# Gadget-Box-ESP8266-Modules.net
KiCad netlist of a schematic drawn in EAGLE
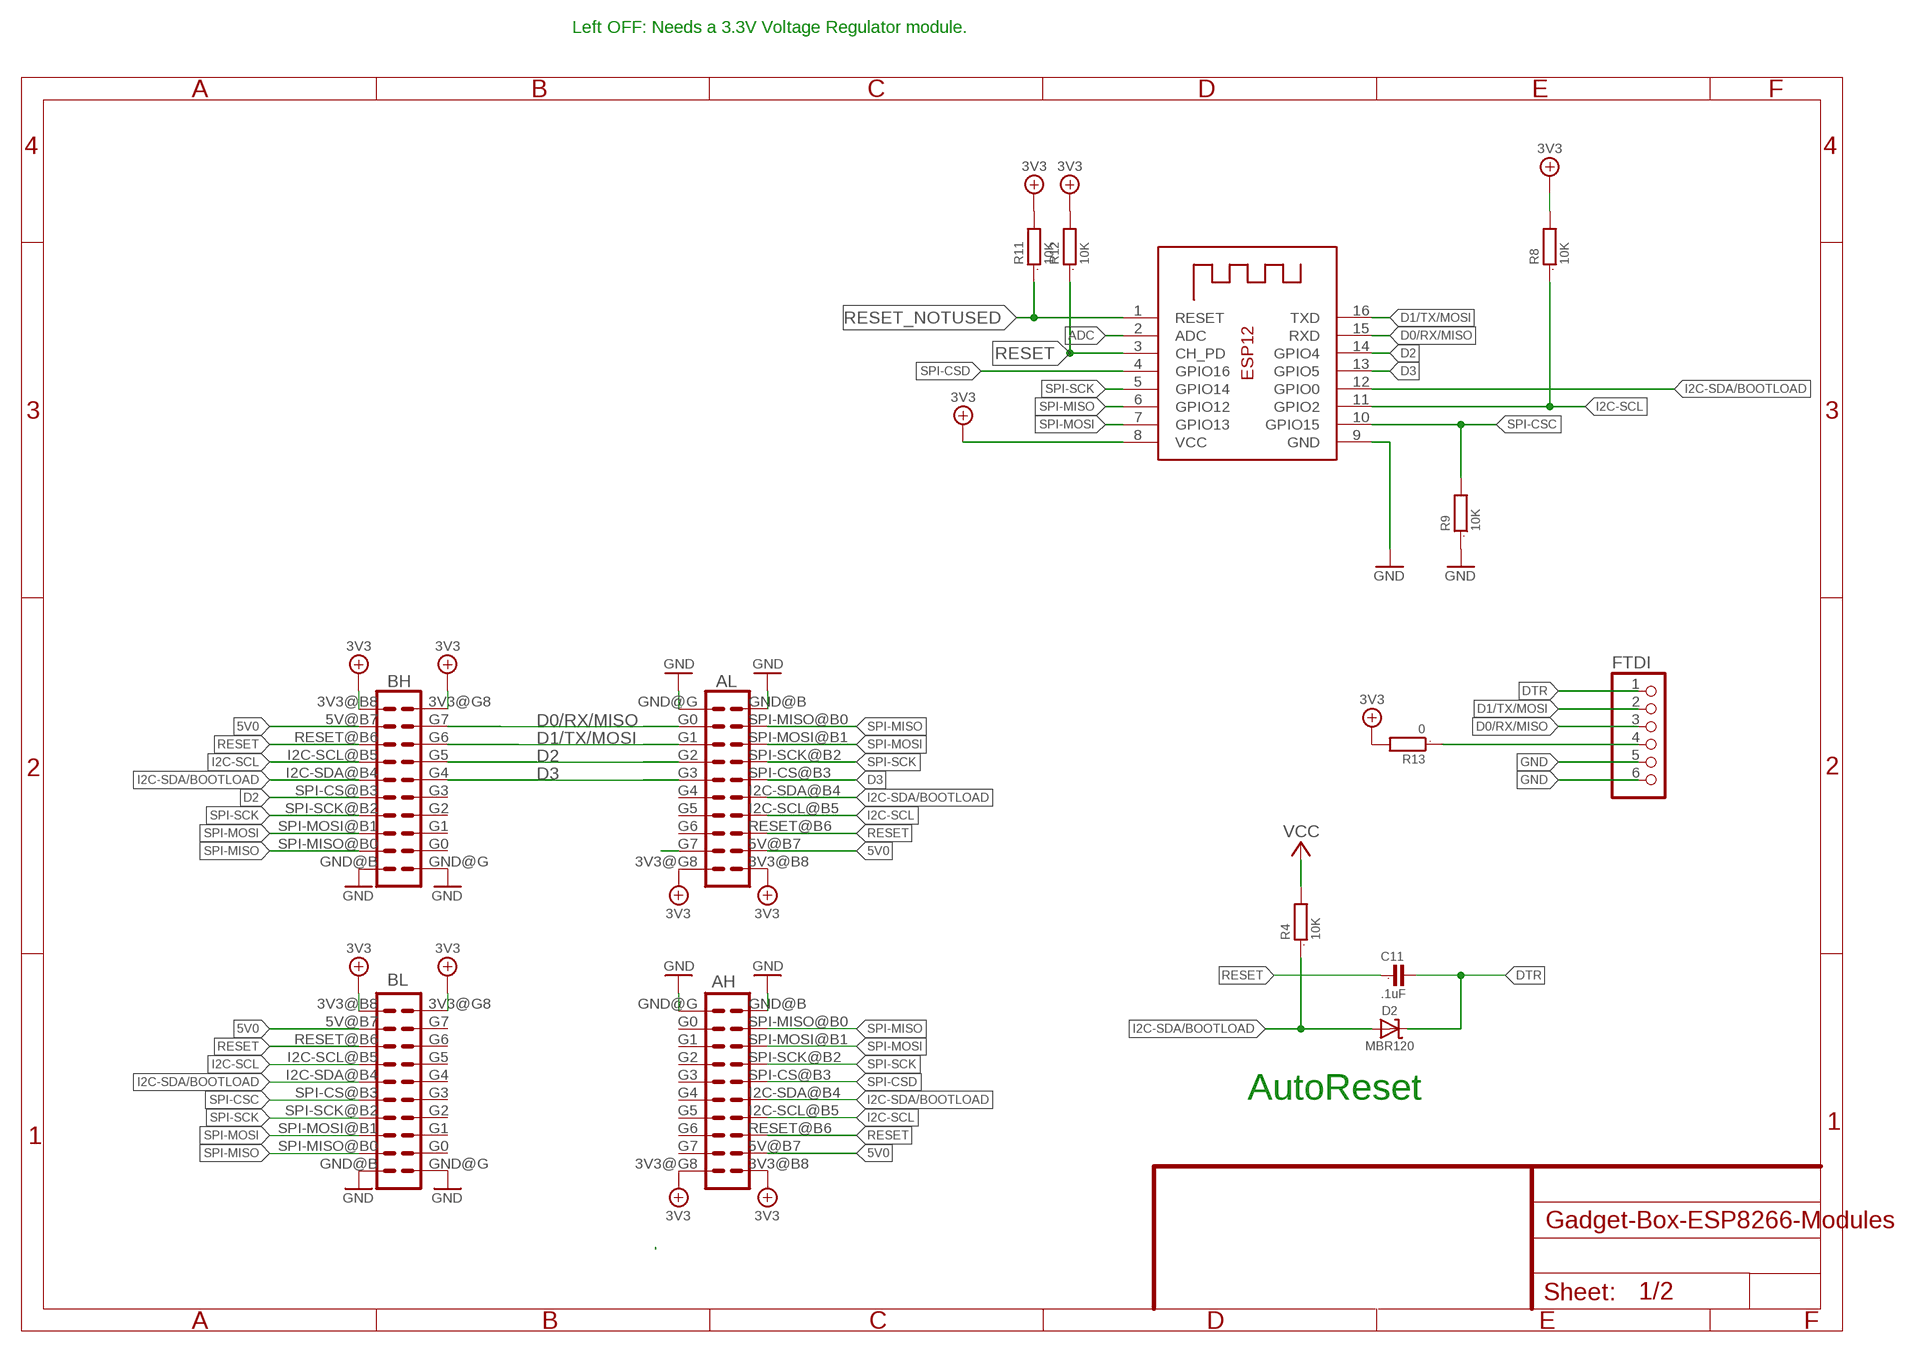
[diagram p0: schematic, sheet 1]
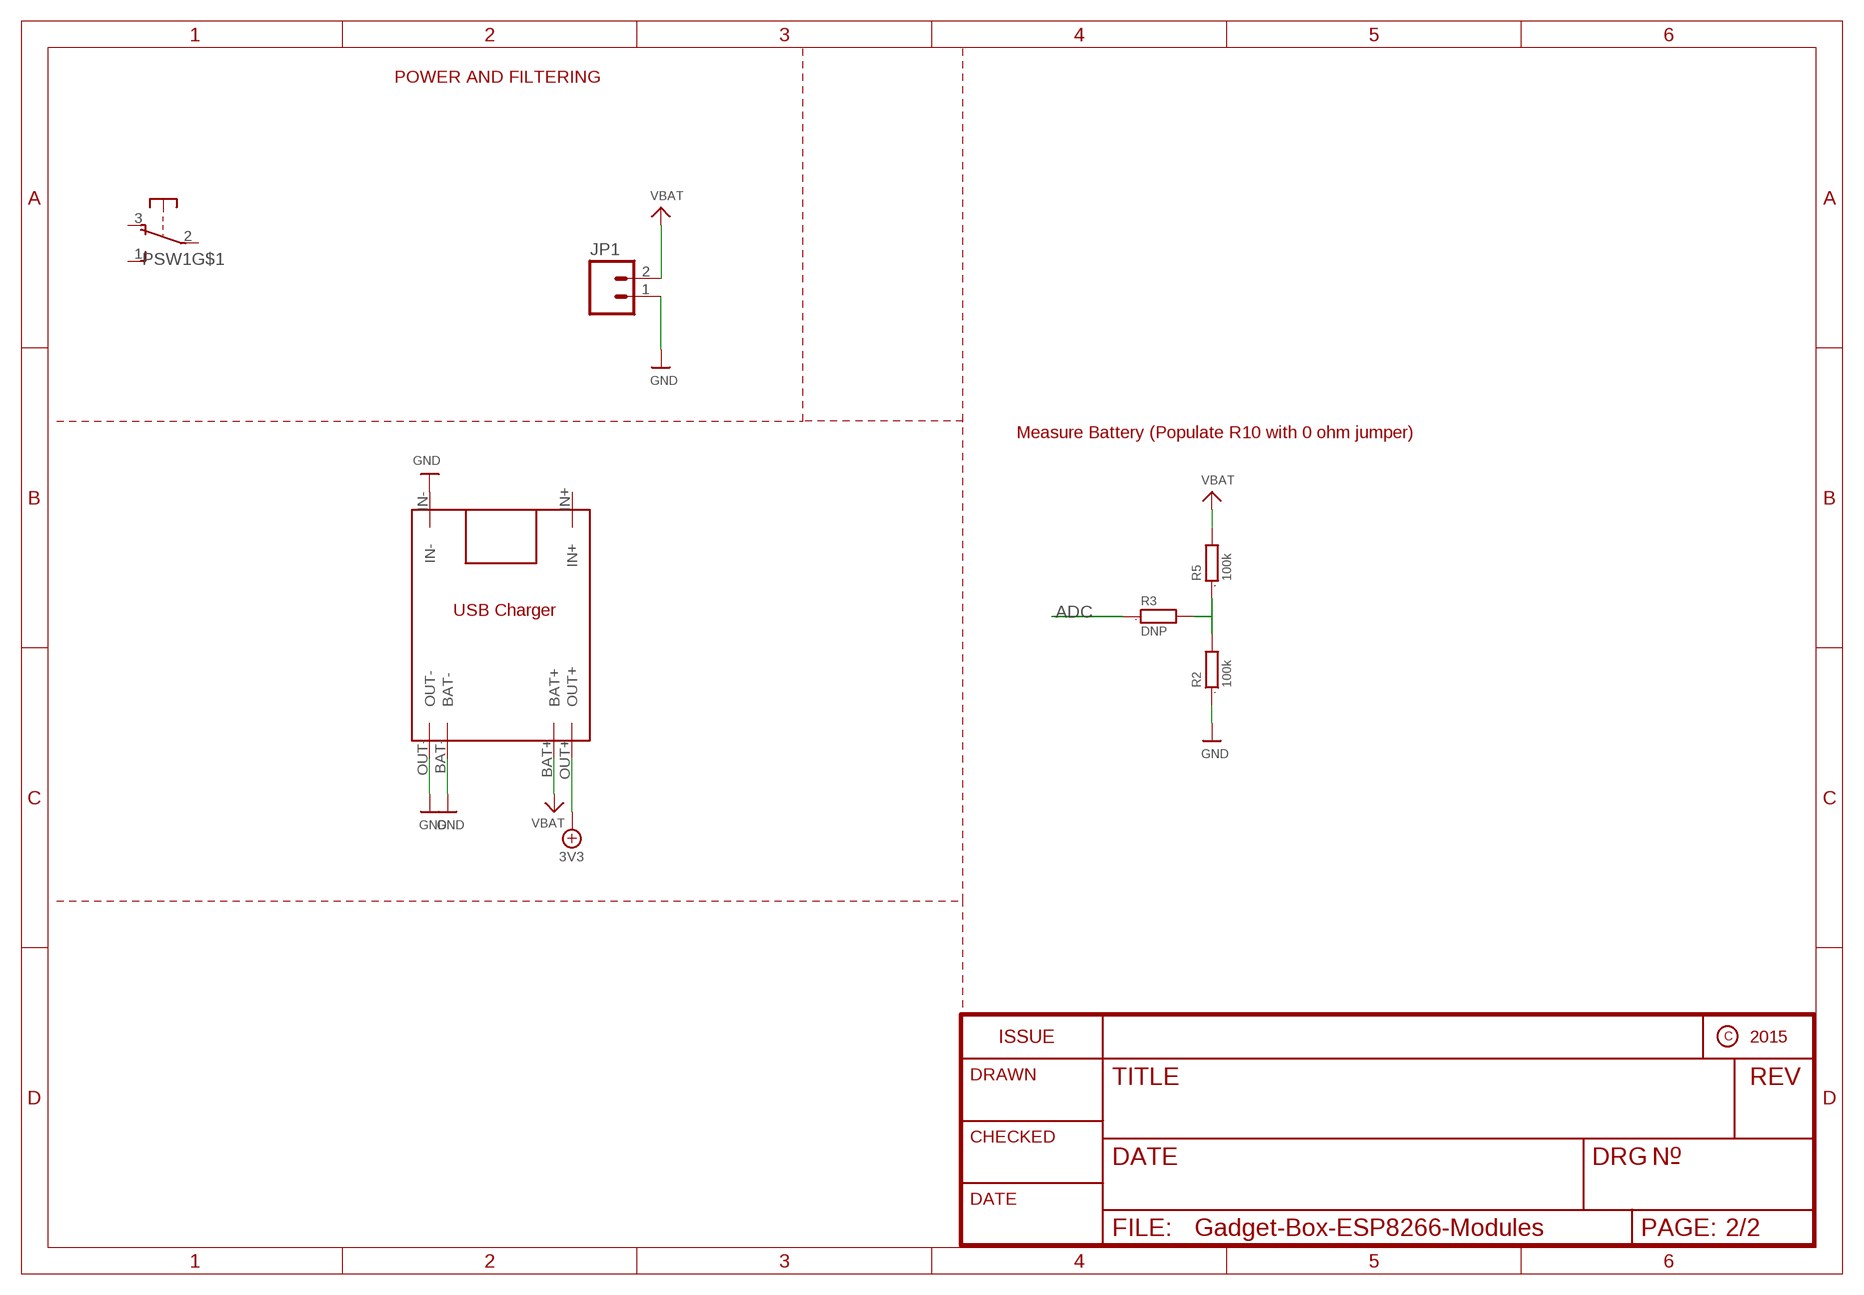
[diagram p1: schematic, sheet 2]

(export (version "E")
  (design (tool "Eeschema 10.0.6"))
  (components
    (comp (ref "JP1")
      (value "M02-JST-2-PTH-NO_SILK")
      (footprint "eagle-import:JST-2-PTH-NS")
      (libsource (lib "eagle-import") (part "M02-JST-2-PTH-NO_SILK"))
    )
    (comp (ref "PSW1")
      (value "OS102011MA1Q")
      (footprint "eagle-import:OS102011MA1Q")
      (fields
        (field (name "PARTNO") "OS102011MA1QN1,C&K Components,dk,CKN9559-ND,SWITCH SLIDE SPDT 100MA 12V , REF72")
      )
      (libsource (lib "eagle-import") (part "OS102011MA1Q"))
    )
    (comp (ref "R2")
      (value "100k")
      (footprint "eagle-import:0603")
      (fields
        (field (name "PARTNO") "RC0603JR-07100KL,YAGEO (VA),dk,311-100KGRCT-ND,RES SMD 100K OHM 5% 1/10W 0603 , REF76")
      )
      (libsource (lib "eagle-import") (part "R0603"))
    )
    (comp (ref "R3")
      (value "DNP")
      (footprint "eagle-import:0603")
      (libsource (lib "eagle-import") (part "R0603"))
    )
    (comp (ref "R5")
      (value "100k")
      (footprint "eagle-import:0603")
      (fields
        (field (name "PARTNO") "RC0603JR-07100KL,YAGEO (VA),dk,311-100KGRCT-ND,RES SMD 100K OHM 5% 1/10W 0603 , REF76")
      )
      (libsource (lib "eagle-import") (part "R0603"))
    )
    (comp (ref "U$1")
      (value "TP4056")
      (footprint "eagle-import:TP4056")
      (libsource (lib "eagle-import") (part "TP4056"))
    )
    (comp (ref "AH")
      (value "ECOGECOG_SLOT")
      (footprint "eagle-import:ECOG")
      (libsource (lib "eagle-import") (part "ECOGECOG_SLOT"))
    )
    (comp (ref "AL")
      (value "ECOGECOG_SLOT")
      (footprint "eagle-import:ECOG")
      (libsource (lib "eagle-import") (part "ECOGECOG_SLOT"))
    )
    (comp (ref "BH")
      (value "ECOGECOG_SLOT")
      (footprint "eagle-import:ECOG")
      (libsource (lib "eagle-import") (part "ECOGECOG_SLOT"))
    )
    (comp (ref "BL")
      (value "ECOGECOG_SLOT")
      (footprint "eagle-import:ECOG")
      (libsource (lib "eagle-import") (part "ECOGECOG_SLOT"))
    )
    (comp (ref "C11")
      (value ".1uF")
      (footprint "eagle-import:0805")
      (fields
        (field (name "PARTNO") "GRM21BR71E104KA01L,MURATA ELECTRONICS (VA),DK,490-1673-1-ND,CAP CER .1UF 25V 10% X7R 0805, REF3")
      )
      (libsource (lib "eagle-import") (part "C0805"))
    )
    (comp (ref "D2")
      (value "MBR120")
      (footprint "eagle-import:SOD-123")
      (fields
        (field (name "PARTNO") "MBR120VLSFT3G,on semiconductor,dk,MBR120VLSFT3GOSCT-ND ,DIODE SCHOTTKY 20V 1A SOD123FL , REF71")
      )
      (libsource (lib "eagle-import") (part "DIODE-SCHOTTKYSOD-123"))
    )
    (comp (ref "FTDI")
      (value "PINHD-1X6")
      (footprint "eagle-import:1X06")
      (libsource (lib "eagle-import") (part "PINHD-1X6"))
    )
    (comp (ref "R4")
      (value "10K")
      (footprint "eagle-import:0805")
      (fields
        (field (name "PARTNO") "RC0805JR-0710KL,YAGEO (VA),dk,311-10KARCT-ND,RES SMD 10K OHM 5% 1/8W 0805, REF63")
      )
      (libsource (lib "eagle-import") (part "R0805"))
    )
    (comp (ref "R8")
      (value "10K")
      (footprint "eagle-import:0805")
      (fields
        (field (name "PARTNO") "RC0805JR-0710KL,YAGEO (VA),dk,311-10KARCT-ND,RES SMD 10K OHM 5% 1/8W 0805, REF63")
      )
      (libsource (lib "eagle-import") (part "R0805"))
    )
    (comp (ref "R9")
      (value "10K")
      (footprint "eagle-import:0805")
      (fields
        (field (name "PARTNO") "RC0805JR-0710KL,YAGEO (VA),dk,311-10KARCT-ND,RES SMD 10K OHM 5% 1/8W 0805, REF63")
      )
      (libsource (lib "eagle-import") (part "R0805"))
    )
    (comp (ref "R11")
      (value "10K")
      (footprint "eagle-import:0805")
      (fields
        (field (name "PARTNO") "RC0805JR-0710KL,YAGEO (VA),dk,311-10KARCT-ND,RES SMD 10K OHM 5% 1/8W 0805, REF63")
      )
      (libsource (lib "eagle-import") (part "R0805"))
    )
    (comp (ref "R12")
      (value "10K")
      (footprint "eagle-import:0805")
      (fields
        (field (name "PARTNO") "RC0805JR-0710KL,YAGEO (VA),dk,311-10KARCT-ND,RES SMD 10K OHM 5% 1/8W 0805, REF63")
      )
      (libsource (lib "eagle-import") (part "R0805"))
    )
    (comp (ref "R13")
      (value "0")
      (footprint "eagle-import:0805")
      (libsource (lib "eagle-import") (part "R0805"))
    )
    (comp (ref "X2")
      (value "ESP-12")
      (footprint "eagle-import:ESP-12")
      (libsource (lib "eagle-import") (part "ESP-12"))
    )
  )
  (nets
    (net (code "1") (name "3V3") (class "Default")
      (node (ref "AH") (pin "3V3@B8") (pinfunction "3V3_3V3@B8") (pintype "passive"))
      (node (ref "AH") (pin "3V3@G8") (pinfunction "3V3_3V3@G8") (pintype "passive"))
      (node (ref "AL") (pin "3V3@B8") (pinfunction "3V3_3V3@B8") (pintype "passive"))
      (node (ref "AL") (pin "3V3@G8") (pinfunction "3V3_3V3@G8") (pintype "passive"))
      (node (ref "BH") (pin "3V3@B8") (pinfunction "3V3_3V3@B8") (pintype "passive"))
      (node (ref "BH") (pin "3V3@G8") (pinfunction "3V3_3V3@G8") (pintype "passive"))
      (node (ref "BL") (pin "3V3@B8") (pinfunction "3V3_3V3@B8") (pintype "passive"))
      (node (ref "BL") (pin "3V3@G8") (pinfunction "3V3_3V3@G8") (pintype "passive"))
      (node (ref "R11") (pin "2") (pinfunction "2_2") (pintype "passive"))
      (node (ref "R12") (pin "2") (pinfunction "2_2") (pintype "passive"))
      (node (ref "R13") (pin "2") (pinfunction "2_2") (pintype "passive"))
      (node (ref "R8") (pin "2") (pinfunction "2_2") (pintype "passive"))
      (node (ref "U$1") (pin "OUT+") (pinfunction "OUT+_OUT+") (pintype "bidirectional"))
      (node (ref "X2") (pin "8") (pinfunction "VCC_8") (pintype "power_in"))
    )
    (net (code "2") (name "5V0") (class "Default")
      (node (ref "AH") (pin "5V@B7") (pinfunction "5V_5V@B7") (pintype "passive"))
      (node (ref "AL") (pin "5V@B7") (pinfunction "5V_5V@B7") (pintype "passive"))
      (node (ref "BH") (pin "5V@B7") (pinfunction "5V_5V@B7") (pintype "passive"))
      (node (ref "BL") (pin "5V@B7") (pinfunction "5V_5V@B7") (pintype "passive"))
    )
    (net (code "3") (name "ADC") (class "Default")
      (node (ref "R3") (pin "1") (pinfunction "1_1") (pintype "passive"))
      (node (ref "X2") (pin "2") (pinfunction "ADC_2") (pintype "passive"))
    )
    (net (code "4") (name "D0{slash}RX{slash}MISO") (class "Default")
      (node (ref "AL") (pin "G0") (pinfunction "G0_G0") (pintype "passive"))
      (node (ref "BH") (pin "G7") (pinfunction "G7_G7") (pintype "passive"))
      (node (ref "FTDI") (pin "3") (pinfunction "3_3") (pintype "passive"))
      (node (ref "X2") (pin "15") (pinfunction "RXD_15") (pintype "input"))
    )
    (net (code "5") (name "D1{slash}TX{slash}MOSI") (class "Default")
      (node (ref "AL") (pin "G1") (pinfunction "G1_G1") (pintype "passive"))
      (node (ref "BH") (pin "G6") (pinfunction "G6_G6") (pintype "passive"))
      (node (ref "FTDI") (pin "2") (pinfunction "2_2") (pintype "passive"))
      (node (ref "X2") (pin "16") (pinfunction "TXD_16") (pintype "output"))
    )
    (net (code "6") (name "D2") (class "Default")
      (node (ref "AL") (pin "G2") (pinfunction "G2_G2") (pintype "passive"))
      (node (ref "BH") (pin "G5") (pinfunction "G5_G5") (pintype "passive"))
      (node (ref "BH") (pin "SPI-CS@B3") (pinfunction "SPI-CS_SPI-CS@B3") (pintype "passive"))
      (node (ref "X2") (pin "14") (pinfunction "GPIO4_14") (pintype "bidirectional"))
    )
    (net (code "7") (name "D3") (class "Default")
      (node (ref "AL") (pin "G3") (pinfunction "G3_G3") (pintype "passive"))
      (node (ref "AL") (pin "SPI-CS@B3") (pinfunction "SPI-CS_SPI-CS@B3") (pintype "passive"))
      (node (ref "BH") (pin "G4") (pinfunction "G4_G4") (pintype "passive"))
      (node (ref "X2") (pin "13") (pinfunction "GPIO5_13") (pintype "bidirectional"))
    )
    (net (code "8") (name "DTR") (class "Default")
      (node (ref "C11") (pin "2") (pinfunction "2_2") (pintype "passive"))
      (node (ref "D2") (pin "C") (pinfunction "C_C") (pintype "passive"))
      (node (ref "FTDI") (pin "1") (pinfunction "1_1") (pintype "passive"))
    )
    (net (code "9") (name "GND") (class "Default")
      (node (ref "AH") (pin "GND@B") (pinfunction "GND_GND@B") (pintype "passive"))
      (node (ref "AH") (pin "GND@G") (pinfunction "GND_GND@G") (pintype "passive"))
      (node (ref "AL") (pin "GND@B") (pinfunction "GND_GND@B") (pintype "passive"))
      (node (ref "AL") (pin "GND@G") (pinfunction "GND_GND@G") (pintype "passive"))
      (node (ref "BH") (pin "GND@B") (pinfunction "GND_GND@B") (pintype "passive"))
      (node (ref "BH") (pin "GND@G") (pinfunction "GND_GND@G") (pintype "passive"))
      (node (ref "BL") (pin "GND@B") (pinfunction "GND_GND@B") (pintype "passive"))
      (node (ref "BL") (pin "GND@G") (pinfunction "GND_GND@G") (pintype "passive"))
      (node (ref "FTDI") (pin "5") (pinfunction "5_5") (pintype "passive"))
      (node (ref "FTDI") (pin "6") (pinfunction "6_6") (pintype "passive"))
      (node (ref "JP1") (pin "1") (pinfunction "1_1") (pintype "passive"))
      (node (ref "R2") (pin "1") (pinfunction "1_1") (pintype "passive"))
      (node (ref "R9") (pin "1") (pinfunction "1_1") (pintype "passive"))
      (node (ref "U$1") (pin "BAT-") (pinfunction "BAT-_BAT-") (pintype "bidirectional"))
      (node (ref "U$1") (pin "IN-") (pinfunction "IN-_IN-") (pintype "bidirectional"))
      (node (ref "U$1") (pin "OUT-") (pinfunction "OUT-_OUT-") (pintype "bidirectional"))
      (node (ref "X2") (pin "9") (pinfunction "GND_9") (pintype "power_in"))
    )
    (net (code "10") (name "I2C-SCL") (class "Default")
      (node (ref "AH") (pin "I2C-SCL@B5") (pinfunction "I2C-SCL_I2C-SCL@B5") (pintype "passive"))
      (node (ref "AL") (pin "I2C-SCL@B5") (pinfunction "I2C-SCL_I2C-SCL@B5") (pintype "passive"))
      (node (ref "BH") (pin "I2C-SCL@B5") (pinfunction "I2C-SCL_I2C-SCL@B5") (pintype "passive"))
      (node (ref "BL") (pin "I2C-SCL@B5") (pinfunction "I2C-SCL_I2C-SCL@B5") (pintype "passive"))
      (node (ref "R8") (pin "1") (pinfunction "1_1") (pintype "passive"))
      (node (ref "X2") (pin "11") (pinfunction "GPIO2_11") (pintype "bidirectional"))
    )
    (net (code "11") (name "I2C-SDA{slash}BOOTLOAD") (class "Default")
      (node (ref "AH") (pin "I2C-SDA@B4") (pinfunction "I2C-SDA_I2C-SDA@B4") (pintype "passive"))
      (node (ref "AL") (pin "I2C-SDA@B4") (pinfunction "I2C-SDA_I2C-SDA@B4") (pintype "passive"))
      (node (ref "BH") (pin "I2C-SDA@B4") (pinfunction "I2C-SDA_I2C-SDA@B4") (pintype "passive"))
      (node (ref "BL") (pin "I2C-SDA@B4") (pinfunction "I2C-SDA_I2C-SDA@B4") (pintype "passive"))
      (node (ref "D2") (pin "A") (pinfunction "A_A") (pintype "passive"))
      (node (ref "R4") (pin "1") (pinfunction "1_1") (pintype "passive"))
      (node (ref "X2") (pin "12") (pinfunction "GPIO0_12") (pintype "bidirectional"))
    )
    (net (code "12") (name "Net-(FTDI-Pad4)") (class "Default")
      (node (ref "FTDI") (pin "4") (pinfunction "4_4") (pintype "passive"))
      (node (ref "R13") (pin "1") (pinfunction "1_1") (pintype "passive"))
    )
    (net (code "13") (name "Net-(R2-Pad2)") (class "Default")
      (node (ref "R2") (pin "2") (pinfunction "2_2") (pintype "passive"))
      (node (ref "R3") (pin "2") (pinfunction "2_2") (pintype "passive"))
      (node (ref "R5") (pin "1") (pinfunction "1_1") (pintype "passive"))
    )
    (net (code "14") (name "RESET") (class "Default")
      (node (ref "AH") (pin "RESET@B6") (pinfunction "RESET_RESET@B6") (pintype "passive"))
      (node (ref "AL") (pin "RESET@B6") (pinfunction "RESET_RESET@B6") (pintype "passive"))
      (node (ref "BH") (pin "RESET@B6") (pinfunction "RESET_RESET@B6") (pintype "passive"))
      (node (ref "BL") (pin "RESET@B6") (pinfunction "RESET_RESET@B6") (pintype "passive"))
      (node (ref "C11") (pin "1") (pinfunction "1_1") (pintype "passive"))
      (node (ref "R12") (pin "1") (pinfunction "1_1") (pintype "passive"))
      (node (ref "X2") (pin "3") (pinfunction "CH_PD_3") (pintype "input"))
    )
    (net (code "15") (name "RESET_NOTUSED") (class "Default")
      (node (ref "R11") (pin "1") (pinfunction "1_1") (pintype "passive"))
      (node (ref "X2") (pin "1") (pinfunction "RESET_1") (pintype "input"))
    )
    (net (code "16") (name "SPI-CSC") (class "Default")
      (node (ref "BL") (pin "SPI-CS@B3") (pinfunction "SPI-CS_SPI-CS@B3") (pintype "passive"))
      (node (ref "R9") (pin "2") (pinfunction "2_2") (pintype "passive"))
      (node (ref "X2") (pin "10") (pinfunction "GPIO15_10") (pintype "bidirectional"))
    )
    (net (code "17") (name "SPI-CSD") (class "Default")
      (node (ref "AH") (pin "SPI-CS@B3") (pinfunction "SPI-CS_SPI-CS@B3") (pintype "passive"))
      (node (ref "X2") (pin "4") (pinfunction "GPIO16_4") (pintype "bidirectional"))
    )
    (net (code "18") (name "SPI-MISO") (class "Default")
      (node (ref "AH") (pin "SPI-MISO@B0") (pinfunction "SPI-MISO_SPI-MISO@B0") (pintype "passive"))
      (node (ref "AL") (pin "SPI-MISO@B0") (pinfunction "SPI-MISO_SPI-MISO@B0") (pintype "passive"))
      (node (ref "BH") (pin "SPI-MISO@B0") (pinfunction "SPI-MISO_SPI-MISO@B0") (pintype "passive"))
      (node (ref "BL") (pin "SPI-MISO@B0") (pinfunction "SPI-MISO_SPI-MISO@B0") (pintype "passive"))
      (node (ref "X2") (pin "6") (pinfunction "GPIO12_6") (pintype "bidirectional"))
    )
    (net (code "19") (name "SPI-MOSI") (class "Default")
      (node (ref "AH") (pin "SPI-MOSI@B1") (pinfunction "SPI-MOSI_SPI-MOSI@B1") (pintype "passive"))
      (node (ref "AL") (pin "SPI-MOSI@B1") (pinfunction "SPI-MOSI_SPI-MOSI@B1") (pintype "passive"))
      (node (ref "BH") (pin "SPI-MOSI@B1") (pinfunction "SPI-MOSI_SPI-MOSI@B1") (pintype "passive"))
      (node (ref "BL") (pin "SPI-MOSI@B1") (pinfunction "SPI-MOSI_SPI-MOSI@B1") (pintype "passive"))
      (node (ref "X2") (pin "7") (pinfunction "GPIO13_7") (pintype "bidirectional"))
    )
    (net (code "20") (name "SPI-SCK") (class "Default")
      (node (ref "AH") (pin "SPI-SCK@B2") (pinfunction "SPI-SCK_SPI-SCK@B2") (pintype "passive"))
      (node (ref "AL") (pin "SPI-SCK@B2") (pinfunction "SPI-SCK_SPI-SCK@B2") (pintype "passive"))
      (node (ref "BH") (pin "SPI-SCK@B2") (pinfunction "SPI-SCK_SPI-SCK@B2") (pintype "passive"))
      (node (ref "BL") (pin "SPI-SCK@B2") (pinfunction "SPI-SCK_SPI-SCK@B2") (pintype "passive"))
      (node (ref "X2") (pin "5") (pinfunction "GPIO14_5") (pintype "bidirectional"))
    )
    (net (code "21") (name "VBAT") (class "Default")
      (node (ref "JP1") (pin "2") (pinfunction "2_2") (pintype "passive"))
      (node (ref "R5") (pin "2") (pinfunction "2_2") (pintype "passive"))
      (node (ref "U$1") (pin "BAT+") (pinfunction "BAT+_BAT+") (pintype "bidirectional"))
    )
    (net (code "22") (name "VCC") (class "Default")
      (node (ref "R4") (pin "2") (pinfunction "2_2") (pintype "passive"))
    )
    (net (code "23") (name "unconnected-(AH-PadG0)") (class "Default")
      (node (ref "AH") (pin "G0") (pinfunction "G0_G0") (pintype "passive"))
    )
    (net (code "24") (name "unconnected-(AH-PadG1)") (class "Default")
      (node (ref "AH") (pin "G1") (pinfunction "G1_G1") (pintype "passive"))
    )
    (net (code "25") (name "unconnected-(AH-PadG2)") (class "Default")
      (node (ref "AH") (pin "G2") (pinfunction "G2_G2") (pintype "passive"))
    )
    (net (code "26") (name "unconnected-(AH-PadG3)") (class "Default")
      (node (ref "AH") (pin "G3") (pinfunction "G3_G3") (pintype "passive"))
    )
    (net (code "27") (name "unconnected-(AH-PadG4)") (class "Default")
      (node (ref "AH") (pin "G4") (pinfunction "G4_G4") (pintype "passive"))
    )
    (net (code "28") (name "unconnected-(AH-PadG5)") (class "Default")
      (node (ref "AH") (pin "G5") (pinfunction "G5_G5") (pintype "passive"))
    )
    (net (code "29") (name "unconnected-(AH-PadG6)") (class "Default")
      (node (ref "AH") (pin "G6") (pinfunction "G6_G6") (pintype "passive"))
    )
    (net (code "30") (name "unconnected-(AH-PadG7)") (class "Default")
      (node (ref "AH") (pin "G7") (pinfunction "G7_G7") (pintype "passive"))
    )
    (net (code "31") (name "unconnected-(AL-PadG4)") (class "Default")
      (node (ref "AL") (pin "G4") (pinfunction "G4_G4") (pintype "passive"))
    )
    (net (code "32") (name "unconnected-(AL-PadG5)") (class "Default")
      (node (ref "AL") (pin "G5") (pinfunction "G5_G5") (pintype "passive"))
    )
    (net (code "33") (name "unconnected-(AL-PadG6)") (class "Default")
      (node (ref "AL") (pin "G6") (pinfunction "G6_G6") (pintype "passive"))
    )
    (net (code "34") (name "unconnected-(AL-PadG7)") (class "Default")
      (node (ref "AL") (pin "G7") (pinfunction "G7_G7") (pintype "passive"))
    )
    (net (code "35") (name "unconnected-(BH-PadG0)") (class "Default")
      (node (ref "BH") (pin "G0") (pinfunction "G0_G0") (pintype "passive"))
    )
    (net (code "36") (name "unconnected-(BH-PadG1)") (class "Default")
      (node (ref "BH") (pin "G1") (pinfunction "G1_G1") (pintype "passive"))
    )
    (net (code "37") (name "unconnected-(BH-PadG2)") (class "Default")
      (node (ref "BH") (pin "G2") (pinfunction "G2_G2") (pintype "passive"))
    )
    (net (code "38") (name "unconnected-(BH-PadG3)") (class "Default")
      (node (ref "BH") (pin "G3") (pinfunction "G3_G3") (pintype "passive"))
    )
    (net (code "39") (name "unconnected-(BL-PadG0)") (class "Default")
      (node (ref "BL") (pin "G0") (pinfunction "G0_G0") (pintype "passive"))
    )
    (net (code "40") (name "unconnected-(BL-PadG1)") (class "Default")
      (node (ref "BL") (pin "G1") (pinfunction "G1_G1") (pintype "passive"))
    )
    (net (code "41") (name "unconnected-(BL-PadG2)") (class "Default")
      (node (ref "BL") (pin "G2") (pinfunction "G2_G2") (pintype "passive"))
    )
    (net (code "42") (name "unconnected-(BL-PadG3)") (class "Default")
      (node (ref "BL") (pin "G3") (pinfunction "G3_G3") (pintype "passive"))
    )
    (net (code "43") (name "unconnected-(BL-PadG4)") (class "Default")
      (node (ref "BL") (pin "G4") (pinfunction "G4_G4") (pintype "passive"))
    )
    (net (code "44") (name "unconnected-(BL-PadG5)") (class "Default")
      (node (ref "BL") (pin "G5") (pinfunction "G5_G5") (pintype "passive"))
    )
    (net (code "45") (name "unconnected-(BL-PadG6)") (class "Default")
      (node (ref "BL") (pin "G6") (pinfunction "G6_G6") (pintype "passive"))
    )
    (net (code "46") (name "unconnected-(BL-PadG7)") (class "Default")
      (node (ref "BL") (pin "G7") (pinfunction "G7_G7") (pintype "passive"))
    )
    (net (code "47") (name "unconnected-(PSW1A-O-Pad3)") (class "Default")
      (node (ref "PSW1") (pin "3") (pinfunction "O_3") (pintype "passive"))
    )
    (net (code "48") (name "unconnected-(PSW1A-P-Pad2)") (class "Default")
      (node (ref "PSW1") (pin "2") (pinfunction "P_2") (pintype "passive"))
    )
    (net (code "49") (name "unconnected-(PSW1A-S-Pad1)") (class "Default")
      (node (ref "PSW1") (pin "1") (pinfunction "S_1") (pintype "passive"))
    )
    (net (code "50") (name "unconnected-(U$1-PadIN+)") (class "Default")
      (node (ref "U$1") (pin "IN+") (pinfunction "IN+_IN+") (pintype "bidirectional"))
    )
  )
)
